# SolenoidController.net
KiCad netlist of a schematic drawn in EAGLE
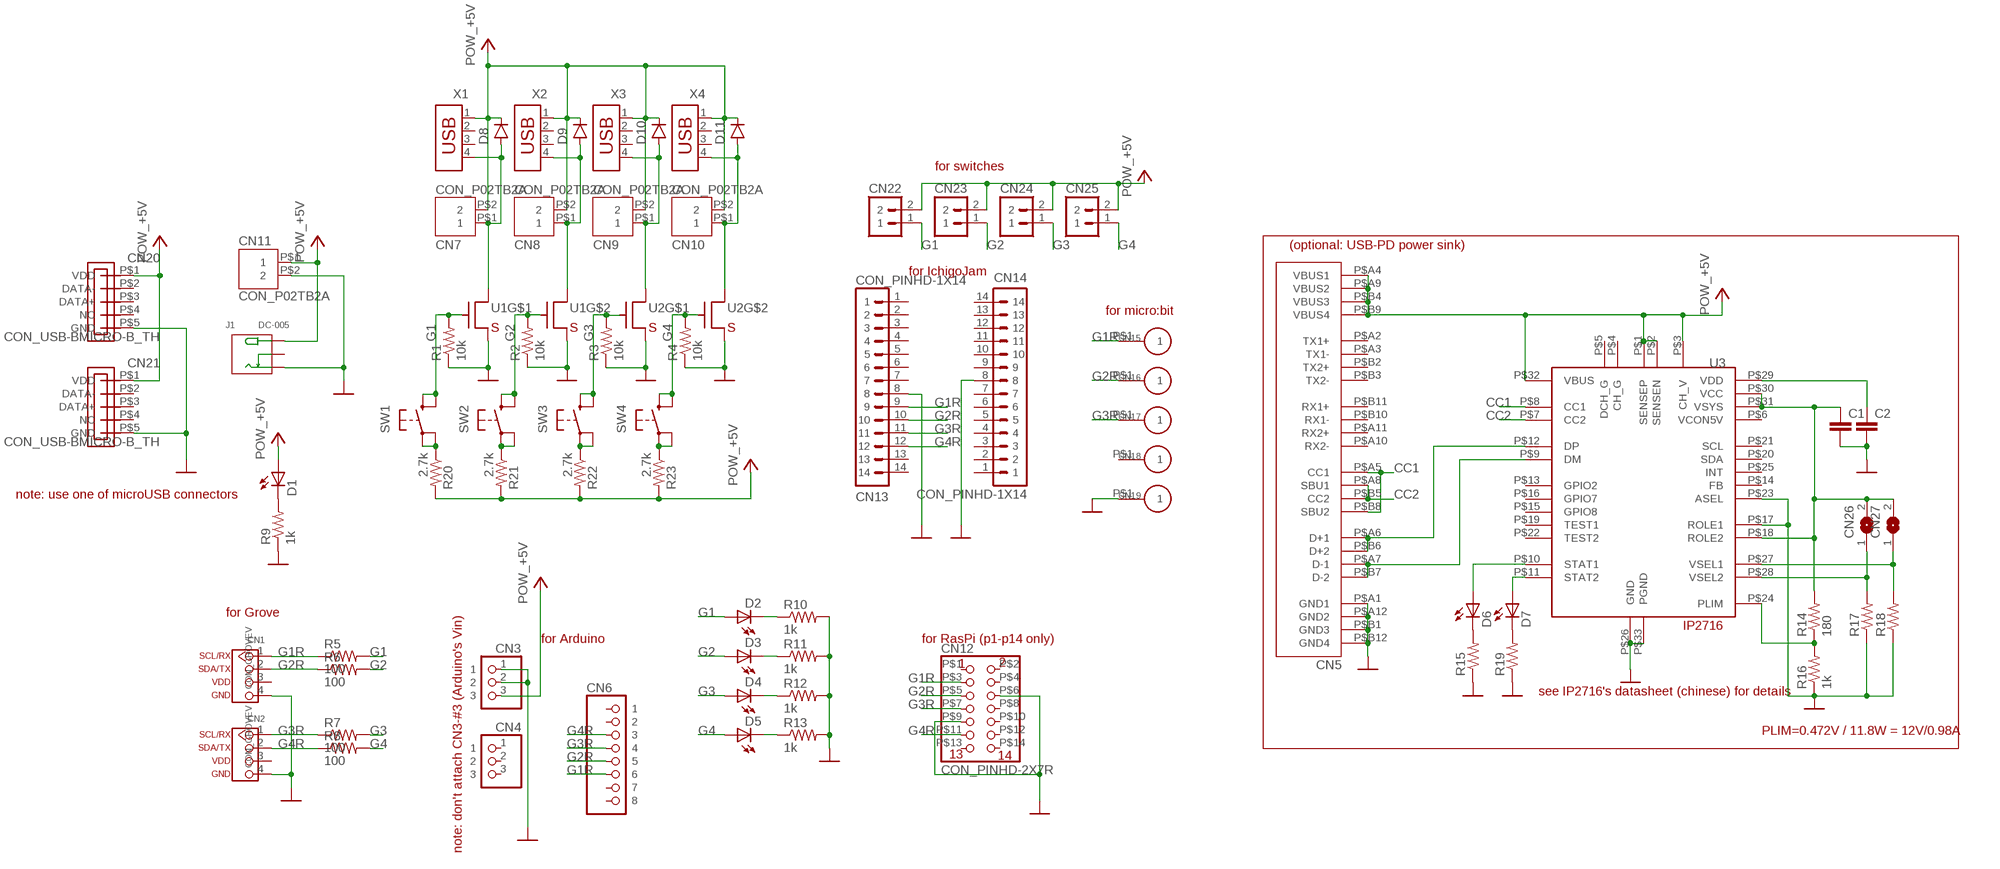
[diagram p0: schematic, sheet 1]

(export (version "E")
  (design (tool "Eeschema 10.0.6"))
  (components
    (comp (ref "C1")
      (value "CAP0603")
      (footprint "eagle-import:0603")
      (libsource (lib "eagle-import") (part "CAP0603"))
    )
    (comp (ref "C2")
      (value "CAP0603")
      (footprint "eagle-import:0603")
      (libsource (lib "eagle-import") (part "CAP0603"))
    )
    (comp (ref "CN1")
      (value "CON_GROVEV")
      (footprint "eagle-import:CON_GROVE_V")
      (libsource (lib "eagle-import") (part "CON_GROVEV"))
    )
    (comp (ref "CN2")
      (value "CON_GROVEV")
      (footprint "eagle-import:CON_GROVE_V")
      (libsource (lib "eagle-import") (part "CON_GROVEV"))
    )
    (comp (ref "CN3")
      (value "CON_PINHD-1X3R")
      (footprint "eagle-import:1X03R")
      (libsource (lib "eagle-import") (part "CON_PINHD-1X3R"))
    )
    (comp (ref "CN4")
      (value "CON_PINHD-1X3R")
      (footprint "eagle-import:1X03R")
      (libsource (lib "eagle-import") (part "CON_PINHD-1X3R"))
    )
    (comp (ref "CN5")
      (value "CON_USB-C")
      (footprint "eagle-import:USB-C_24P")
      (libsource (lib "eagle-import") (part "CON_USB-C"))
    )
    (comp (ref "CN6")
      (value "CON_PINHD-1X8R")
      (footprint "eagle-import:1X08R")
      (libsource (lib "eagle-import") (part "CON_PINHD-1X8R"))
    )
    (comp (ref "CN7")
      (value "CON_P02TB2A")
      (footprint "eagle-import:TERM_BLOCK_2P")
      (libsource (lib "eagle-import") (part "CON_P02TB2A"))
    )
    (comp (ref "CN8")
      (value "CON_P02TB2A")
      (footprint "eagle-import:TERM_BLOCK_2P")
      (libsource (lib "eagle-import") (part "CON_P02TB2A"))
    )
    (comp (ref "CN9")
      (value "CON_P02TB2A")
      (footprint "eagle-import:TERM_BLOCK_2P")
      (libsource (lib "eagle-import") (part "CON_P02TB2A"))
    )
    (comp (ref "CN10")
      (value "CON_P02TB2A")
      (footprint "eagle-import:TERM_BLOCK_2P")
      (libsource (lib "eagle-import") (part "CON_P02TB2A"))
    )
    (comp (ref "CN11")
      (value "CON_P02TB2A")
      (footprint "eagle-import:TERM_BLOCK_2P")
      (libsource (lib "eagle-import") (part "CON_P02TB2A"))
    )
    (comp (ref "CN12")
      (value "CON_PINHD-2X7R")
      (footprint "eagle-import:2X7R")
      (libsource (lib "eagle-import") (part "CON_PINHD-2X7R"))
    )
    (comp (ref "CN13")
      (value "CON_PINHD-1X14")
      (footprint "eagle-import:1X14")
      (libsource (lib "eagle-import") (part "CON_PINHD-1X14"))
    )
    (comp (ref "CN14")
      (value "CON_PINHD-1X14")
      (footprint "eagle-import:1X14")
      (libsource (lib "eagle-import") (part "CON_PINHD-1X14"))
    )
    (comp (ref "CN15")
      (value "CON_P01TH04MM")
      (footprint "eagle-import:TH4MM")
      (libsource (lib "eagle-import") (part "CON_P01TH04MM"))
    )
    (comp (ref "CN16")
      (value "CON_P01TH04MM")
      (footprint "eagle-import:TH4MM")
      (libsource (lib "eagle-import") (part "CON_P01TH04MM"))
    )
    (comp (ref "CN17")
      (value "CON_P01TH04MM")
      (footprint "eagle-import:TH4MM")
      (libsource (lib "eagle-import") (part "CON_P01TH04MM"))
    )
    (comp (ref "CN18")
      (value "CON_P01TH04MM")
      (footprint "eagle-import:TH4MM")
      (libsource (lib "eagle-import") (part "CON_P01TH04MM"))
    )
    (comp (ref "CN19")
      (value "CON_P01TH04MM")
      (footprint "eagle-import:TH4MM")
      (libsource (lib "eagle-import") (part "CON_P01TH04MM"))
    )
    (comp (ref "CN20")
      (value "CON_USB-BMICRO-B_TH")
      (footprint "eagle-import:USB-MICROB-TH")
      (libsource (lib "eagle-import") (part "CON_USB-BMICRO-B_TH"))
    )
    (comp (ref "CN21")
      (value "CON_USB-BMICRO-B_TH")
      (footprint "eagle-import:USB-MICROB-TH")
      (libsource (lib "eagle-import") (part "CON_USB-BMICRO-B_TH"))
    )
    (comp (ref "CN22")
      (value "CON_PINHD-1X2PTH")
      (footprint "eagle-import:SPARKFUN_1X02")
      (libsource (lib "eagle-import") (part "CON_PINHD-1X2PTH"))
    )
    (comp (ref "CN23")
      (value "CON_PINHD-1X2PTH")
      (footprint "eagle-import:SPARKFUN_1X02")
      (libsource (lib "eagle-import") (part "CON_PINHD-1X2PTH"))
    )
    (comp (ref "CN24")
      (value "CON_PINHD-1X2PTH")
      (footprint "eagle-import:SPARKFUN_1X02")
      (libsource (lib "eagle-import") (part "CON_PINHD-1X2PTH"))
    )
    (comp (ref "CN25")
      (value "CON_PINHD-1X2PTH")
      (footprint "eagle-import:SPARKFUN_1X02")
      (libsource (lib "eagle-import") (part "CON_PINHD-1X2PTH"))
    )
    (comp (ref "CN26")
      (value "JUMPER_SJ")
      (footprint "eagle-import:JUMPER_SJ")
      (libsource (lib "eagle-import") (part "JUMPER_SJ"))
    )
    (comp (ref "CN27")
      (value "JUMPER_SJ")
      (footprint "eagle-import:JUMPER_SJ")
      (libsource (lib "eagle-import") (part "JUMPER_SJ"))
    )
    (comp (ref "D1")
      (value "LED5MM")
      (footprint "eagle-import:SPARKFUN_LED5MM")
      (libsource (lib "eagle-import") (part "LED5MM"))
    )
    (comp (ref "D2")
      (value "LED5MM")
      (footprint "eagle-import:SPARKFUN_LED5MM")
      (libsource (lib "eagle-import") (part "LED5MM"))
    )
    (comp (ref "D3")
      (value "LED5MM")
      (footprint "eagle-import:SPARKFUN_LED5MM")
      (libsource (lib "eagle-import") (part "LED5MM"))
    )
    (comp (ref "D4")
      (value "LED5MM")
      (footprint "eagle-import:SPARKFUN_LED5MM")
      (libsource (lib "eagle-import") (part "LED5MM"))
    )
    (comp (ref "D5")
      (value "LED5MM")
      (footprint "eagle-import:SPARKFUN_LED5MM")
      (libsource (lib "eagle-import") (part "LED5MM"))
    )
    (comp (ref "D6")
      (value "LED0603")
      (footprint "eagle-import:SPARKFUN_LED-0603")
      (libsource (lib "eagle-import") (part "LED0603"))
    )
    (comp (ref "D7")
      (value "LED0603")
      (footprint "eagle-import:SPARKFUN_LED-0603")
      (libsource (lib "eagle-import") (part "LED0603"))
    )
    (comp (ref "D8")
      (value "DIODESOD123FL")
      (footprint "eagle-import:SOD123FL")
      (libsource (lib "eagle-import") (part "DIODESOD123FL"))
    )
    (comp (ref "D9")
      (value "DIODESOD123FL")
      (footprint "eagle-import:SOD123FL")
      (libsource (lib "eagle-import") (part "DIODESOD123FL"))
    )
    (comp (ref "D10")
      (value "DIODESOD123FL")
      (footprint "eagle-import:SOD123FL")
      (libsource (lib "eagle-import") (part "DIODESOD123FL"))
    )
    (comp (ref "D11")
      (value "DIODESOD123FL")
      (footprint "eagle-import:SOD123FL")
      (libsource (lib "eagle-import") (part "DIODESOD123FL"))
    )
    (comp (ref "J1")
      (value "DC-005")
      (footprint "eagle-import:DCJ3P-14.2X11.0X9.0MM")
      (libsource (lib "eagle-import") (part "CONN-POWER-JACK-2.1MM(DC-005)"))
    )
    (comp (ref "R1")
      (value "10k")
      (footprint "eagle-import:0603")
      (libsource (lib "eagle-import") (part "RES0603"))
    )
    (comp (ref "R2")
      (value "10k")
      (footprint "eagle-import:0603")
      (libsource (lib "eagle-import") (part "RES0603"))
    )
    (comp (ref "R3")
      (value "10k")
      (footprint "eagle-import:0603")
      (libsource (lib "eagle-import") (part "RES0603"))
    )
    (comp (ref "R4")
      (value "10k")
      (footprint "eagle-import:0603")
      (libsource (lib "eagle-import") (part "RES0603"))
    )
    (comp (ref "R5")
      (value "100")
      (footprint "eagle-import:0603")
      (libsource (lib "eagle-import") (part "RES0603"))
    )
    (comp (ref "R6")
      (value "100")
      (footprint "eagle-import:0603")
      (libsource (lib "eagle-import") (part "RES0603"))
    )
    (comp (ref "R7")
      (value "100")
      (footprint "eagle-import:0603")
      (libsource (lib "eagle-import") (part "RES0603"))
    )
    (comp (ref "R8")
      (value "100")
      (footprint "eagle-import:0603")
      (libsource (lib "eagle-import") (part "RES0603"))
    )
    (comp (ref "R9")
      (value "1k")
      (footprint "eagle-import:0603")
      (libsource (lib "eagle-import") (part "RES0603"))
    )
    (comp (ref "R10")
      (value "1k")
      (footprint "eagle-import:0603")
      (libsource (lib "eagle-import") (part "RES0603"))
    )
    (comp (ref "R11")
      (value "1k")
      (footprint "eagle-import:0603")
      (libsource (lib "eagle-import") (part "RES0603"))
    )
    (comp (ref "R12")
      (value "1k")
      (footprint "eagle-import:0603")
      (libsource (lib "eagle-import") (part "RES0603"))
    )
    (comp (ref "R13")
      (value "1k")
      (footprint "eagle-import:0603")
      (libsource (lib "eagle-import") (part "RES0603"))
    )
    (comp (ref "R14")
      (value "180")
      (footprint "eagle-import:0603")
      (libsource (lib "eagle-import") (part "RES0603"))
    )
    (comp (ref "R15")
      (value "RES0603")
      (footprint "eagle-import:0603")
      (libsource (lib "eagle-import") (part "RES0603"))
    )
    (comp (ref "R16")
      (value "1k")
      (footprint "eagle-import:0603")
      (libsource (lib "eagle-import") (part "RES0603"))
    )
    (comp (ref "R17")
      (value "RES0603")
      (footprint "eagle-import:0603")
      (libsource (lib "eagle-import") (part "RES0603"))
    )
    (comp (ref "R18")
      (value "RES0603")
      (footprint "eagle-import:0603")
      (libsource (lib "eagle-import") (part "RES0603"))
    )
    (comp (ref "R19")
      (value "RES0603")
      (footprint "eagle-import:0603")
      (libsource (lib "eagle-import") (part "RES0603"))
    )
    (comp (ref "R20")
      (value "2.7k")
      (footprint "eagle-import:0603")
      (libsource (lib "eagle-import") (part "RES0603"))
    )
    (comp (ref "R21")
      (value "2.7k")
      (footprint "eagle-import:0603")
      (libsource (lib "eagle-import") (part "RES0603"))
    )
    (comp (ref "R22")
      (value "2.7k")
      (footprint "eagle-import:0603")
      (libsource (lib "eagle-import") (part "RES0603"))
    )
    (comp (ref "R23")
      (value "2.7k")
      (footprint "eagle-import:0603")
      (libsource (lib "eagle-import") (part "RES0603"))
    )
    (comp (ref "SW1")
      (value "SW_TACTSMD_B3FS4")
      (footprint "eagle-import:SW_B3FS-4")
      (libsource (lib "eagle-import") (part "SW_TACTSMD_B3FS4"))
    )
    (comp (ref "SW2")
      (value "SW_TACTSMD_B3FS4")
      (footprint "eagle-import:SW_B3FS-4")
      (libsource (lib "eagle-import") (part "SW_TACTSMD_B3FS4"))
    )
    (comp (ref "SW3")
      (value "SW_TACTSMD_B3FS4")
      (footprint "eagle-import:SW_B3FS-4")
      (libsource (lib "eagle-import") (part "SW_TACTSMD_B3FS4"))
    )
    (comp (ref "SW4")
      (value "SW_TACTSMD_B3FS4")
      (footprint "eagle-import:SW_B3FS-4")
      (libsource (lib "eagle-import") (part "SW_TACTSMD_B3FS4"))
    )
    (comp (ref "U1")
      (value "TR_NMOS_IRF7103")
      (footprint "eagle-import:SO08")
      (libsource (lib "eagle-import") (part "TR_NMOS_IRF7103"))
    )
    (comp (ref "U2")
      (value "TR_NMOS_IRF7103")
      (footprint "eagle-import:SO08")
      (libsource (lib "eagle-import") (part "TR_NMOS_IRF7103"))
    )
    (comp (ref "U3")
      (value "PMU_IP2716")
      (footprint "eagle-import:QFN32E")
      (libsource (lib "eagle-import") (part "PMU_IP2716"))
    )
    (comp (ref "X1")
      (value "CON_USB-A")
      (footprint "eagle-import:USB-A")
      (libsource (lib "eagle-import") (part "CON_USB-A"))
    )
    (comp (ref "X2")
      (value "CON_USB-A")
      (footprint "eagle-import:USB-A")
      (libsource (lib "eagle-import") (part "CON_USB-A"))
    )
    (comp (ref "X3")
      (value "CON_USB-A")
      (footprint "eagle-import:USB-A")
      (libsource (lib "eagle-import") (part "CON_USB-A"))
    )
    (comp (ref "X4")
      (value "CON_USB-A")
      (footprint "eagle-import:USB-A")
      (libsource (lib "eagle-import") (part "CON_USB-A"))
    )
  )
  (nets
    (net (code "1") (name "/CC1") (class "Default")
      (node (ref "CN5") (pin "P$A5") (pinfunction "CC1_P$A5") (pintype "bidirectional"))
      (node (ref "CN5") (pin "P$B8") (pinfunction "SBU2_P$B8") (pintype "bidirectional"))
      (node (ref "U3") (pin "P$8") (pinfunction "CC1_P$8") (pintype "bidirectional"))
    )
    (net (code "2") (name "/CC2") (class "Default")
      (node (ref "CN5") (pin "P$A8") (pinfunction "SBU1_P$A8") (pintype "bidirectional"))
      (node (ref "CN5") (pin "P$B5") (pinfunction "CC2_P$B5") (pintype "bidirectional"))
      (node (ref "U3") (pin "P$7") (pinfunction "CC2_P$7") (pintype "bidirectional"))
    )
    (net (code "3") (name "/G1") (class "Default")
      (node (ref "CN22") (pin "1") (pinfunction "1_1") (pintype "passive"))
      (node (ref "D2") (pin "A") (pinfunction "A_A") (pintype "passive"))
      (node (ref "R1") (pin "2") (pinfunction "2_2") (pintype "passive"))
      (node (ref "R5") (pin "2") (pinfunction "2_2") (pintype "passive"))
      (node (ref "SW1") (pin "P$3") (pinfunction "S_P$3") (pintype "passive"))
      (node (ref "SW1") (pin "P$4") (pinfunction "S1_P$4") (pintype "passive"))
      (node (ref "U1") (pin "2") (pinfunction "G_2") (pintype "bidirectional"))
    )
    (net (code "4") (name "/G1R") (class "Default")
      (node (ref "CN1") (pin "1") (pinfunction "1_1") (pintype "bidirectional"))
      (node (ref "CN12") (pin "P$3") (pinfunction "3_P$3") (pintype "passive"))
      (node (ref "CN13") (pin "9") (pinfunction "9_9") (pintype "passive"))
      (node (ref "CN15") (pin "P$1") (pinfunction "1_P$1") (pintype "bidirectional"))
      (node (ref "CN6") (pin "6") (pinfunction "6_6") (pintype "passive"))
      (node (ref "R5") (pin "1") (pinfunction "1_1") (pintype "passive"))
    )
    (net (code "5") (name "/G2") (class "Default")
      (node (ref "CN23") (pin "1") (pinfunction "1_1") (pintype "passive"))
      (node (ref "D3") (pin "A") (pinfunction "A_A") (pintype "passive"))
      (node (ref "R2") (pin "2") (pinfunction "2_2") (pintype "passive"))
      (node (ref "R6") (pin "2") (pinfunction "2_2") (pintype "passive"))
      (node (ref "SW2") (pin "P$3") (pinfunction "S_P$3") (pintype "passive"))
      (node (ref "SW2") (pin "P$4") (pinfunction "S1_P$4") (pintype "passive"))
      (node (ref "U1") (pin "4") (pinfunction "G_4") (pintype "bidirectional"))
    )
    (net (code "6") (name "/G2R") (class "Default")
      (node (ref "CN1") (pin "2") (pinfunction "2_2") (pintype "bidirectional"))
      (node (ref "CN12") (pin "P$5") (pinfunction "5_P$5") (pintype "passive"))
      (node (ref "CN13") (pin "10") (pinfunction "10_10") (pintype "passive"))
      (node (ref "CN16") (pin "P$1") (pinfunction "1_P$1") (pintype "bidirectional"))
      (node (ref "CN6") (pin "5") (pinfunction "5_5") (pintype "passive"))
      (node (ref "R6") (pin "1") (pinfunction "1_1") (pintype "passive"))
    )
    (net (code "7") (name "/G3") (class "Default")
      (node (ref "CN24") (pin "1") (pinfunction "1_1") (pintype "passive"))
      (node (ref "D4") (pin "A") (pinfunction "A_A") (pintype "passive"))
      (node (ref "R3") (pin "2") (pinfunction "2_2") (pintype "passive"))
      (node (ref "R7") (pin "2") (pinfunction "2_2") (pintype "passive"))
      (node (ref "SW3") (pin "P$3") (pinfunction "S_P$3") (pintype "passive"))
      (node (ref "SW3") (pin "P$4") (pinfunction "S1_P$4") (pintype "passive"))
      (node (ref "U2") (pin "2") (pinfunction "G_2") (pintype "bidirectional"))
    )
    (net (code "8") (name "/G3R") (class "Default")
      (node (ref "CN12") (pin "P$7") (pinfunction "7_P$7") (pintype "passive"))
      (node (ref "CN13") (pin "11") (pinfunction "11_11") (pintype "passive"))
      (node (ref "CN17") (pin "P$1") (pinfunction "1_P$1") (pintype "bidirectional"))
      (node (ref "CN2") (pin "1") (pinfunction "1_1") (pintype "bidirectional"))
      (node (ref "CN6") (pin "4") (pinfunction "4_4") (pintype "passive"))
      (node (ref "R7") (pin "1") (pinfunction "1_1") (pintype "passive"))
    )
    (net (code "9") (name "/G4") (class "Default")
      (node (ref "CN25") (pin "1") (pinfunction "1_1") (pintype "passive"))
      (node (ref "D5") (pin "A") (pinfunction "A_A") (pintype "passive"))
      (node (ref "R4") (pin "2") (pinfunction "2_2") (pintype "passive"))
      (node (ref "R8") (pin "2") (pinfunction "2_2") (pintype "passive"))
      (node (ref "SW4") (pin "P$3") (pinfunction "S_P$3") (pintype "passive"))
      (node (ref "SW4") (pin "P$4") (pinfunction "S1_P$4") (pintype "passive"))
      (node (ref "U2") (pin "4") (pinfunction "G_4") (pintype "bidirectional"))
    )
    (net (code "10") (name "/G4R") (class "Default")
      (node (ref "CN12") (pin "P$11") (pinfunction "11_P$11") (pintype "passive"))
      (node (ref "CN13") (pin "12") (pinfunction "12_12") (pintype "passive"))
      (node (ref "CN2") (pin "2") (pinfunction "2_2") (pintype "bidirectional"))
      (node (ref "CN6") (pin "3") (pinfunction "3_3") (pintype "passive"))
      (node (ref "R8") (pin "1") (pinfunction "1_1") (pintype "passive"))
    )
    (net (code "11") (name "Net-(CN5-D+1)") (class "Default")
      (node (ref "CN5") (pin "P$A6") (pinfunction "D+1_P$A6") (pintype "bidirectional"))
      (node (ref "CN5") (pin "P$B6") (pinfunction "D+2_P$B6") (pintype "bidirectional"))
      (node (ref "U3") (pin "P$12") (pinfunction "DP_P$12") (pintype "bidirectional"))
    )
    (net (code "12") (name "Net-(CN5-D-1)") (class "Default")
      (node (ref "CN5") (pin "P$A7") (pinfunction "D-1_P$A7") (pintype "bidirectional"))
      (node (ref "CN5") (pin "P$B7") (pinfunction "D-2_P$B7") (pintype "bidirectional"))
      (node (ref "U3") (pin "P$9") (pinfunction "DM_P$9") (pintype "bidirectional"))
    )
    (net (code "13") (name "Net-(CN7-1)") (class "Default")
      (node (ref "CN7") (pin "P$1") (pinfunction "1_P$1") (pintype "passive"))
      (node (ref "D8") (pin "P$A") (pinfunction "P$A_P$A") (pintype "bidirectional"))
      (node (ref "U1") (pin "7") (pinfunction "D_7") (pintype "bidirectional"))
      (node (ref "X1") (pin "4") (pinfunction "4_4") (pintype "passive"))
    )
    (net (code "14") (name "Net-(CN8-1)") (class "Default")
      (node (ref "CN8") (pin "P$1") (pinfunction "1_P$1") (pintype "passive"))
      (node (ref "D9") (pin "P$A") (pinfunction "P$A_P$A") (pintype "bidirectional"))
      (node (ref "U1") (pin "5") (pinfunction "D_5") (pintype "bidirectional"))
      (node (ref "X2") (pin "4") (pinfunction "4_4") (pintype "passive"))
    )
    (net (code "15") (name "Net-(CN9-1)") (class "Default")
      (node (ref "CN9") (pin "P$1") (pinfunction "1_P$1") (pintype "passive"))
      (node (ref "D10") (pin "P$A") (pinfunction "P$A_P$A") (pintype "bidirectional"))
      (node (ref "U2") (pin "7") (pinfunction "D_7") (pintype "bidirectional"))
      (node (ref "X3") (pin "4") (pinfunction "4_4") (pintype "passive"))
    )
    (net (code "16") (name "Net-(CN10-1)") (class "Default")
      (node (ref "CN10") (pin "P$1") (pinfunction "1_P$1") (pintype "passive"))
      (node (ref "D11") (pin "P$A") (pinfunction "P$A_P$A") (pintype "bidirectional"))
      (node (ref "U2") (pin "5") (pinfunction "D_5") (pintype "bidirectional"))
      (node (ref "X4") (pin "4") (pinfunction "4_4") (pintype "passive"))
    )
    (net (code "17") (name "Net-(D1-C)") (class "Default")
      (node (ref "D1") (pin "K") (pinfunction "C_K") (pintype "passive"))
      (node (ref "R9") (pin "2") (pinfunction "2_2") (pintype "passive"))
    )
    (net (code "18") (name "Net-(D2-C)") (class "Default")
      (node (ref "D2") (pin "K") (pinfunction "C_K") (pintype "passive"))
      (node (ref "R10") (pin "1") (pinfunction "1_1") (pintype "passive"))
    )
    (net (code "19") (name "Net-(D3-C)") (class "Default")
      (node (ref "D3") (pin "K") (pinfunction "C_K") (pintype "passive"))
      (node (ref "R11") (pin "1") (pinfunction "1_1") (pintype "passive"))
    )
    (net (code "20") (name "Net-(D4-C)") (class "Default")
      (node (ref "D4") (pin "K") (pinfunction "C_K") (pintype "passive"))
      (node (ref "R12") (pin "1") (pinfunction "1_1") (pintype "passive"))
    )
    (net (code "21") (name "Net-(D5-C)") (class "Default")
      (node (ref "D5") (pin "K") (pinfunction "C_K") (pintype "passive"))
      (node (ref "R13") (pin "1") (pinfunction "1_1") (pintype "passive"))
    )
    (net (code "22") (name "Net-(D6-PadC)") (class "Default")
      (node (ref "D6") (pin "C") (pinfunction "C_C") (pintype "passive"))
      (node (ref "R15") (pin "2") (pinfunction "2_2") (pintype "passive"))
    )
    (net (code "23") (name "Net-(D7-PadC)") (class "Default")
      (node (ref "D7") (pin "C") (pinfunction "C_C") (pintype "passive"))
      (node (ref "R19") (pin "2") (pinfunction "2_2") (pintype "passive"))
    )
    (net (code "24") (name "Net-(SW1-P)") (class "Default")
      (node (ref "R20") (pin "1") (pinfunction "1_1") (pintype "passive"))
      (node (ref "SW1") (pin "P$1") (pinfunction "P_P$1") (pintype "passive"))
      (node (ref "SW1") (pin "P$2") (pinfunction "P1_P$2") (pintype "passive"))
    )
    (net (code "25") (name "Net-(SW2-P)") (class "Default")
      (node (ref "R21") (pin "1") (pinfunction "1_1") (pintype "passive"))
      (node (ref "SW2") (pin "P$1") (pinfunction "P_P$1") (pintype "passive"))
      (node (ref "SW2") (pin "P$2") (pinfunction "P1_P$2") (pintype "passive"))
    )
    (net (code "26") (name "Net-(SW3-P)") (class "Default")
      (node (ref "R22") (pin "1") (pinfunction "1_1") (pintype "passive"))
      (node (ref "SW3") (pin "P$1") (pinfunction "P_P$1") (pintype "passive"))
      (node (ref "SW3") (pin "P$2") (pinfunction "P1_P$2") (pintype "passive"))
    )
    (net (code "27") (name "Net-(SW4-P)") (class "Default")
      (node (ref "R23") (pin "1") (pinfunction "1_1") (pintype "passive"))
      (node (ref "SW4") (pin "P$1") (pinfunction "P_P$1") (pintype "passive"))
      (node (ref "SW4") (pin "P$2") (pinfunction "P1_P$2") (pintype "passive"))
    )
    (net (code "28") (name "Net-(U3-PLIM)") (class "Default")
      (node (ref "R14") (pin "1") (pinfunction "1_1") (pintype "passive"))
      (node (ref "R16") (pin "2") (pinfunction "2_2") (pintype "passive"))
      (node (ref "U3") (pin "P$24") (pinfunction "PLIM_P$24") (pintype "bidirectional"))
    )
    (net (code "29") (name "Net-(U3-ROLE2)") (class "Default")
      (node (ref "C1") (pin "1") (pinfunction "1_1") (pintype "passive"))
      (node (ref "CN26") (pin "2") (pinfunction "2_2") (pintype "passive"))
      (node (ref "CN27") (pin "2") (pinfunction "2_2") (pintype "passive"))
      (node (ref "R14") (pin "2") (pinfunction "2_2") (pintype "passive"))
      (node (ref "U3") (pin "P$18") (pinfunction "ROLE2_P$18") (pintype "bidirectional"))
      (node (ref "U3") (pin "P$30") (pinfunction "VCC_P$30") (pintype "bidirectional"))
      (node (ref "U3") (pin "P$31") (pinfunction "VSYS_P$31") (pintype "bidirectional"))
    )
    (net (code "30") (name "Net-(U3-STAT1)") (class "Default")
      (node (ref "D6") (pin "A") (pinfunction "A_A") (pintype "passive"))
      (node (ref "U3") (pin "P$10") (pinfunction "STAT1_P$10") (pintype "bidirectional"))
    )
    (net (code "31") (name "Net-(U3-STAT2)") (class "Default")
      (node (ref "D7") (pin "A") (pinfunction "A_A") (pintype "passive"))
      (node (ref "U3") (pin "P$11") (pinfunction "STAT2_P$11") (pintype "bidirectional"))
    )
    (net (code "32") (name "Net-(U3-VDD)") (class "Default")
      (node (ref "C2") (pin "1") (pinfunction "1_1") (pintype "passive"))
      (node (ref "U3") (pin "P$29") (pinfunction "VDD_P$29") (pintype "bidirectional"))
    )
    (net (code "33") (name "Net-(U3-VSEL1)") (class "Default")
      (node (ref "CN27") (pin "1") (pinfunction "1_1") (pintype "passive"))
      (node (ref "R18") (pin "2") (pinfunction "2_2") (pintype "passive"))
      (node (ref "U3") (pin "P$27") (pinfunction "VSEL1_P$27") (pintype "bidirectional"))
    )
    (net (code "34") (name "Net-(U3-VSEL2)") (class "Default")
      (node (ref "CN26") (pin "1") (pinfunction "1_1") (pintype "passive"))
      (node (ref "R17") (pin "2") (pinfunction "2_2") (pintype "passive"))
      (node (ref "U3") (pin "P$28") (pinfunction "VSEL2_P$28") (pintype "bidirectional"))
    )
    (net (code "35") (name "POW_+5V") (class "Default")
      (node (ref "CN10") (pin "P$2") (pinfunction "2_P$2") (pintype "passive"))
      (node (ref "CN11") (pin "P$1") (pinfunction "1_P$1") (pintype "passive"))
      (node (ref "CN20") (pin "P$1") (pinfunction "VDD_P$1") (pintype "power_in"))
      (node (ref "CN21") (pin "P$1") (pinfunction "VDD_P$1") (pintype "power_in"))
      (node (ref "CN22") (pin "2") (pinfunction "2_2") (pintype "passive"))
      (node (ref "CN23") (pin "2") (pinfunction "2_2") (pintype "passive"))
      (node (ref "CN24") (pin "2") (pinfunction "2_2") (pintype "passive"))
      (node (ref "CN25") (pin "2") (pinfunction "2_2") (pintype "passive"))
      (node (ref "CN3") (pin "3") (pinfunction "3_3") (pintype "passive"))
      (node (ref "CN5") (pin "P$A4") (pinfunction "VBUS1_P$A4") (pintype "bidirectional"))
      (node (ref "CN5") (pin "P$A9") (pinfunction "VBUS2_P$A9") (pintype "bidirectional"))
      (node (ref "CN5") (pin "P$B4") (pinfunction "VBUS3_P$B4") (pintype "bidirectional"))
      (node (ref "CN5") (pin "P$B9") (pinfunction "VBUS4_P$B9") (pintype "bidirectional"))
      (node (ref "CN7") (pin "P$2") (pinfunction "2_P$2") (pintype "passive"))
      (node (ref "CN8") (pin "P$2") (pinfunction "2_P$2") (pintype "passive"))
      (node (ref "CN9") (pin "P$2") (pinfunction "2_P$2") (pintype "passive"))
      (node (ref "D1") (pin "A") (pinfunction "A_A") (pintype "passive"))
      (node (ref "D10") (pin "P$K") (pinfunction "P$K_P$K") (pintype "bidirectional"))
      (node (ref "D11") (pin "P$K") (pinfunction "P$K_P$K") (pintype "bidirectional"))
      (node (ref "D8") (pin "P$K") (pinfunction "P$K_P$K") (pintype "bidirectional"))
      (node (ref "D9") (pin "P$K") (pinfunction "P$K_P$K") (pintype "bidirectional"))
      (node (ref "J1") (pin "+") (pinfunction "+_+") (pintype "bidirectional"))
      (node (ref "R20") (pin "2") (pinfunction "2_2") (pintype "passive"))
      (node (ref "R21") (pin "2") (pinfunction "2_2") (pintype "passive"))
      (node (ref "R22") (pin "2") (pinfunction "2_2") (pintype "passive"))
      (node (ref "R23") (pin "2") (pinfunction "2_2") (pintype "passive"))
      (node (ref "U3") (pin "P$1") (pinfunction "SENSEP_P$1") (pintype "bidirectional"))
      (node (ref "U3") (pin "P$2") (pinfunction "SENSEN_P$2") (pintype "bidirectional"))
      (node (ref "U3") (pin "P$3") (pinfunction "CH_V_P$3") (pintype "bidirectional"))
      (node (ref "U3") (pin "P$32") (pinfunction "VBUS_P$32") (pintype "bidirectional"))
      (node (ref "X1") (pin "1") (pinfunction "1_1") (pintype "passive"))
      (node (ref "X2") (pin "1") (pinfunction "1_1") (pintype "passive"))
      (node (ref "X3") (pin "1") (pinfunction "1_1") (pintype "passive"))
      (node (ref "X4") (pin "1") (pinfunction "1_1") (pintype "passive"))
    )
    (net (code "36") (name "POW_GND") (class "Default")
      (node (ref "C1") (pin "2") (pinfunction "2_2") (pintype "passive"))
      (node (ref "C2") (pin "2") (pinfunction "2_2") (pintype "passive"))
      (node (ref "CN1") (pin "4") (pinfunction "4_4") (pintype "bidirectional"))
      (node (ref "CN11") (pin "P$2") (pinfunction "2_P$2") (pintype "passive"))
      (node (ref "CN12") (pin "P$6") (pinfunction "6_P$6") (pintype "passive"))
      (node (ref "CN12") (pin "P$9") (pinfunction "9_P$9") (pintype "passive"))
      (node (ref "CN13") (pin "8") (pinfunction "8_8") (pintype "passive"))
      (node (ref "CN14") (pin "8") (pinfunction "8_8") (pintype "passive"))
      (node (ref "CN19") (pin "P$1") (pinfunction "1_P$1") (pintype "bidirectional"))
      (node (ref "CN2") (pin "4") (pinfunction "4_4") (pintype "bidirectional"))
      (node (ref "CN20") (pin "P$5") (pinfunction "GND_P$5") (pintype "power_in"))
      (node (ref "CN21") (pin "P$5") (pinfunction "GND_P$5") (pintype "power_in"))
      (node (ref "CN3") (pin "1") (pinfunction "1_1") (pintype "passive"))
      (node (ref "CN3") (pin "2") (pinfunction "2_2") (pintype "passive"))
      (node (ref "CN5") (pin "P$A1") (pinfunction "GND1_P$A1") (pintype "bidirectional"))
      (node (ref "CN5") (pin "P$A12") (pinfunction "GND2_P$A12") (pintype "bidirectional"))
      (node (ref "CN5") (pin "P$B1") (pinfunction "GND3_P$B1") (pintype "bidirectional"))
      (node (ref "CN5") (pin "P$B12") (pinfunction "GND4_P$B12") (pintype "bidirectional"))
      (node (ref "J1") (pin "-1") (pinfunction "-_-1") (pintype "bidirectional"))
      (node (ref "R1") (pin "1") (pinfunction "1_1") (pintype "passive"))
      (node (ref "R10") (pin "2") (pinfunction "2_2") (pintype "passive"))
      (node (ref "R11") (pin "2") (pinfunction "2_2") (pintype "passive"))
      (node (ref "R12") (pin "2") (pinfunction "2_2") (pintype "passive"))
      (node (ref "R13") (pin "2") (pinfunction "2_2") (pintype "passive"))
      (node (ref "R15") (pin "1") (pinfunction "1_1") (pintype "passive"))
      (node (ref "R16") (pin "1") (pinfunction "1_1") (pintype "passive"))
      (node (ref "R17") (pin "1") (pinfunction "1_1") (pintype "passive"))
      (node (ref "R18") (pin "1") (pinfunction "1_1") (pintype "passive"))
      (node (ref "R19") (pin "1") (pinfunction "1_1") (pintype "passive"))
      (node (ref "R2") (pin "1") (pinfunction "1_1") (pintype "passive"))
      (node (ref "R3") (pin "1") (pinfunction "1_1") (pintype "passive"))
      (node (ref "R4") (pin "1") (pinfunction "1_1") (pintype "passive"))
      (node (ref "R9") (pin "1") (pinfunction "1_1") (pintype "passive"))
      (node (ref "U1") (pin "1") (pinfunction "S_1") (pintype "bidirectional"))
      (node (ref "U1") (pin "3") (pinfunction "S_3") (pintype "bidirectional"))
      (node (ref "U2") (pin "1") (pinfunction "S_1") (pintype "bidirectional"))
      (node (ref "U2") (pin "3") (pinfunction "S_3") (pintype "bidirectional"))
      (node (ref "U3") (pin "P$17") (pinfunction "ROLE1_P$17") (pintype "bidirectional"))
      (node (ref "U3") (pin "P$23") (pinfunction "ASEL_P$23") (pintype "bidirectional"))
      (node (ref "U3") (pin "P$26") (pinfunction "GND_P$26") (pintype "bidirectional"))
      (node (ref "U3") (pin "P$33") (pinfunction "PGND_P$33") (pintype "bidirectional"))
    )
    (net (code "37") (name "unconnected-(CN1-Pad3)") (class "Default")
      (node (ref "CN1") (pin "3") (pinfunction "3_3") (pintype "bidirectional"))
    )
    (net (code "38") (name "unconnected-(CN2-Pad3)") (class "Default")
      (node (ref "CN2") (pin "3") (pinfunction "3_3") (pintype "bidirectional"))
    )
    (net (code "39") (name "unconnected-(CN4-Pad1)") (class "Default")
      (node (ref "CN4") (pin "1") (pinfunction "1_1") (pintype "passive"))
    )
    (net (code "40") (name "unconnected-(CN4-Pad2)") (class "Default")
      (node (ref "CN4") (pin "2") (pinfunction "2_2") (pintype "passive"))
    )
    (net (code "41") (name "unconnected-(CN4-Pad3)") (class "Default")
      (node (ref "CN4") (pin "3") (pinfunction "3_3") (pintype "passive"))
    )
    (net (code "42") (name "unconnected-(CN5-RX1+-PadP$B11)") (class "Default")
      (node (ref "CN5") (pin "P$B11") (pinfunction "RX1+_P$B11") (pintype "bidirectional"))
    )
    (net (code "43") (name "unconnected-(CN5-RX1--PadP$B10)") (class "Default")
      (node (ref "CN5") (pin "P$B10") (pinfunction "RX1-_P$B10") (pintype "bidirectional"))
    )
    (net (code "44") (name "unconnected-(CN5-RX2+-PadP$A11)") (class "Default")
      (node (ref "CN5") (pin "P$A11") (pinfunction "RX2+_P$A11") (pintype "bidirectional"))
    )
    (net (code "45") (name "unconnected-(CN5-RX2--PadP$A10)") (class "Default")
      (node (ref "CN5") (pin "P$A10") (pinfunction "RX2-_P$A10") (pintype "bidirectional"))
    )
    (net (code "46") (name "unconnected-(CN5-TX1+-PadP$A2)") (class "Default")
      (node (ref "CN5") (pin "P$A2") (pinfunction "TX1+_P$A2") (pintype "bidirectional"))
    )
    (net (code "47") (name "unconnected-(CN5-TX1--PadP$A3)") (class "Default")
      (node (ref "CN5") (pin "P$A3") (pinfunction "TX1-_P$A3") (pintype "bidirectional"))
    )
    (net (code "48") (name "unconnected-(CN5-TX2+-PadP$B2)") (class "Default")
      (node (ref "CN5") (pin "P$B2") (pinfunction "TX2+_P$B2") (pintype "bidirectional"))
    )
    (net (code "49") (name "unconnected-(CN5-TX2--PadP$B3)") (class "Default")
      (node (ref "CN5") (pin "P$B3") (pinfunction "TX2-_P$B3") (pintype "bidirectional"))
    )
    (net (code "50") (name "unconnected-(CN6-Pad1)") (class "Default")
      (node (ref "CN6") (pin "1") (pinfunction "1_1") (pintype "passive"))
    )
    (net (code "51") (name "unconnected-(CN6-Pad2)") (class "Default")
      (node (ref "CN6") (pin "2") (pinfunction "2_2") (pintype "passive"))
    )
    (net (code "52") (name "unconnected-(CN6-Pad7)") (class "Default")
      (node (ref "CN6") (pin "7") (pinfunction "7_7") (pintype "passive"))
    )
    (net (code "53") (name "unconnected-(CN6-Pad8)") (class "Default")
      (node (ref "CN6") (pin "8") (pinfunction "8_8") (pintype "passive"))
    )
    (net (code "54") (name "unconnected-(CN12-1-PadP$1)") (class "Default")
      (node (ref "CN12") (pin "P$1") (pinfunction "1_P$1") (pintype "passive"))
    )
    (net (code "55") (name "unconnected-(CN12-2-PadP$2)") (class "Default")
      (node (ref "CN12") (pin "P$2") (pinfunction "2_P$2") (pintype "passive"))
    )
    (net (code "56") (name "unconnected-(CN12-4-PadP$4)") (class "Default")
      (node (ref "CN12") (pin "P$4") (pinfunction "4_P$4") (pintype "passive"))
    )
    (net (code "57") (name "unconnected-(CN12-8-PadP$8)") (class "Default")
      (node (ref "CN12") (pin "P$8") (pinfunction "8_P$8") (pintype "passive"))
    )
    (net (code "58") (name "unconnected-(CN12-10-PadP$10)") (class "Default")
      (node (ref "CN12") (pin "P$10") (pinfunction "10_P$10") (pintype "passive"))
    )
    (net (code "59") (name "unconnected-(CN12-12-PadP$12)") (class "Default")
      (node (ref "CN12") (pin "P$12") (pinfunction "12_P$12") (pintype "passive"))
    )
    (net (code "60") (name "unconnected-(CN12-13-PadP$13)") (class "Default")
      (node (ref "CN12") (pin "P$13") (pinfunction "13_P$13") (pintype "passive"))
    )
    (net (code "61") (name "unconnected-(CN12-14-PadP$14)") (class "Default")
      (node (ref "CN12") (pin "P$14") (pinfunction "14_P$14") (pintype "passive"))
    )
    (net (code "62") (name "unconnected-(CN13-Pad1)") (class "Default")
      (node (ref "CN13") (pin "1") (pinfunction "1_1") (pintype "passive"))
    )
    (net (code "63") (name "unconnected-(CN13-Pad2)") (class "Default")
      (node (ref "CN13") (pin "2") (pinfunction "2_2") (pintype "passive"))
    )
    (net (code "64") (name "unconnected-(CN13-Pad3)") (class "Default")
      (node (ref "CN13") (pin "3") (pinfunction "3_3") (pintype "passive"))
    )
    (net (code "65") (name "unconnected-(CN13-Pad4)") (class "Default")
      (node (ref "CN13") (pin "4") (pinfunction "4_4") (pintype "passive"))
    )
    (net (code "66") (name "unconnected-(CN13-Pad5)") (class "Default")
      (node (ref "CN13") (pin "5") (pinfunction "5_5") (pintype "passive"))
    )
    (net (code "67") (name "unconnected-(CN13-Pad6)") (class "Default")
      (node (ref "CN13") (pin "6") (pinfunction "6_6") (pintype "passive"))
    )
    (net (code "68") (name "unconnected-(CN13-Pad7)") (class "Default")
      (node (ref "CN13") (pin "7") (pinfunction "7_7") (pintype "passive"))
    )
    (net (code "69") (name "unconnected-(CN13-Pad13)") (class "Default")
      (node (ref "CN13") (pin "13") (pinfunction "13_13") (pintype "passive"))
    )
    (net (code "70") (name "unconnected-(CN13-Pad14)") (class "Default")
      (node (ref "CN13") (pin "14") (pinfunction "14_14") (pintype "passive"))
    )
    (net (code "71") (name "unconnected-(CN14-Pad1)") (class "Default")
      (node (ref "CN14") (pin "1") (pinfunction "1_1") (pintype "passive"))
    )
    (net (code "72") (name "unconnected-(CN14-Pad2)") (class "Default")
      (node (ref "CN14") (pin "2") (pinfunction "2_2") (pintype "passive"))
    )
    (net (code "73") (name "unconnected-(CN14-Pad3)") (class "Default")
      (node (ref "CN14") (pin "3") (pinfunction "3_3") (pintype "passive"))
    )
    (net (code "74") (name "unconnected-(CN14-Pad4)") (class "Default")
      (node (ref "CN14") (pin "4") (pinfunction "4_4") (pintype "passive"))
    )
    (net (code "75") (name "unconnected-(CN14-Pad5)") (class "Default")
      (node (ref "CN14") (pin "5") (pinfunction "5_5") (pintype "passive"))
    )
    (net (code "76") (name "unconnected-(CN14-Pad6)") (class "Default")
      (node (ref "CN14") (pin "6") (pinfunction "6_6") (pintype "passive"))
    )
    (net (code "77") (name "unconnected-(CN14-Pad7)") (class "Default")
      (node (ref "CN14") (pin "7") (pinfunction "7_7") (pintype "passive"))
    )
    (net (code "78") (name "unconnected-(CN14-Pad9)") (class "Default")
      (node (ref "CN14") (pin "9") (pinfunction "9_9") (pintype "passive"))
    )
    (net (code "79") (name "unconnected-(CN14-Pad10)") (class "Default")
      (node (ref "CN14") (pin "10") (pinfunction "10_10") (pintype "passive"))
    )
    (net (code "80") (name "unconnected-(CN14-Pad11)") (class "Default")
      (node (ref "CN14") (pin "11") (pinfunction "11_11") (pintype "passive"))
    )
    (net (code "81") (name "unconnected-(CN14-Pad12)") (class "Default")
      (node (ref "CN14") (pin "12") (pinfunction "12_12") (pintype "passive"))
    )
    (net (code "82") (name "unconnected-(CN14-Pad13)") (class "Default")
      (node (ref "CN14") (pin "13") (pinfunction "13_13") (pintype "passive"))
    )
    (net (code "83") (name "unconnected-(CN14-Pad14)") (class "Default")
      (node (ref "CN14") (pin "14") (pinfunction "14_14") (pintype "passive"))
    )
    (net (code "84") (name "unconnected-(CN18-1-PadP$1)") (class "Default")
      (node (ref "CN18") (pin "P$1") (pinfunction "1_P$1") (pintype "bidirectional"))
    )
    (net (code "85") (name "unconnected-(CN20-DATA+-PadP$3)") (class "Default")
      (node (ref "CN20") (pin "P$3") (pinfunction "DATA+_P$3") (pintype "bidirectional"))
    )
    (net (code "86") (name "unconnected-(CN20-DATA--PadP$2)") (class "Default")
      (node (ref "CN20") (pin "P$2") (pinfunction "DATA-_P$2") (pintype "bidirectional"))
    )
    (net (code "87") (name "unconnected-(CN20-NC-PadP$4)") (class "Default")
      (node (ref "CN20") (pin "P$4") (pinfunction "NC_P$4") (pintype "bidirectional"))
    )
    (net (code "88") (name "unconnected-(CN21-DATA+-PadP$3)") (class "Default")
      (node (ref "CN21") (pin "P$3") (pinfunction "DATA+_P$3") (pintype "bidirectional"))
    )
    (net (code "89") (name "unconnected-(CN21-DATA--PadP$2)") (class "Default")
      (node (ref "CN21") (pin "P$2") (pinfunction "DATA-_P$2") (pintype "bidirectional"))
    )
    (net (code "90") (name "unconnected-(CN21-NC-PadP$4)") (class "Default")
      (node (ref "CN21") (pin "P$4") (pinfunction "NC_P$4") (pintype "bidirectional"))
    )
    (net (code "91") (name "unconnected-(J1-CDN-Pad-2)") (class "Default")
      (node (ref "J1") (pin "-2") (pinfunction "CDN_-2") (pintype "bidirectional"))
    )
    (net (code "92") (name "unconnected-(U3-CH_G-PadP$4)") (class "Default")
      (node (ref "U3") (pin "P$4") (pinfunction "CH_G_P$4") (pintype "bidirectional"))
    )
    (net (code "93") (name "unconnected-(U3-DCH_G-PadP$5)") (class "Default")
      (node (ref "U3") (pin "P$5") (pinfunction "DCH_G_P$5") (pintype "bidirectional"))
    )
    (net (code "94") (name "unconnected-(U3-FB-PadP$14)") (class "Default")
      (node (ref "U3") (pin "P$14") (pinfunction "FB_P$14") (pintype "bidirectional"))
    )
    (net (code "95") (name "unconnected-(U3-GPIO2-PadP$13)") (class "Default")
      (node (ref "U3") (pin "P$13") (pinfunction "GPIO2_P$13") (pintype "bidirectional"))
    )
    (net (code "96") (name "unconnected-(U3-GPIO7-PadP$16)") (class "Default")
      (node (ref "U3") (pin "P$16") (pinfunction "GPIO7_P$16") (pintype "bidirectional"))
    )
    (net (code "97") (name "unconnected-(U3-GPIO8-PadP$15)") (class "Default")
      (node (ref "U3") (pin "P$15") (pinfunction "GPIO8_P$15") (pintype "bidirectional"))
    )
    (net (code "98") (name "unconnected-(U3-INT-PadP$25)") (class "Default")
      (node (ref "U3") (pin "P$25") (pinfunction "INT_P$25") (pintype "bidirectional"))
    )
    (net (code "99") (name "unconnected-(U3-SCL-PadP$21)") (class "Default")
      (node (ref "U3") (pin "P$21") (pinfunction "SCL_P$21") (pintype "bidirectional"))
    )
    (net (code "100") (name "unconnected-(U3-SDA-PadP$20)") (class "Default")
      (node (ref "U3") (pin "P$20") (pinfunction "SDA_P$20") (pintype "bidirectional"))
    )
    (net (code "101") (name "unconnected-(U3-TEST1-PadP$19)") (class "Default")
      (node (ref "U3") (pin "P$19") (pinfunction "TEST1_P$19") (pintype "bidirectional"))
    )
    (net (code "102") (name "unconnected-(U3-TEST2-PadP$22)") (class "Default")
      (node (ref "U3") (pin "P$22") (pinfunction "TEST2_P$22") (pintype "bidirectional"))
    )
    (net (code "103") (name "unconnected-(U3-VCON5V-PadP$6)") (class "Default")
      (node (ref "U3") (pin "P$6") (pinfunction "VCON5V_P$6") (pintype "bidirectional"))
    )
    (net (code "104") (name "unconnected-(X1-Pad2)") (class "Default")
      (node (ref "X1") (pin "2") (pinfunction "2_2") (pintype "passive"))
    )
    (net (code "105") (name "unconnected-(X1-Pad3)") (class "Default")
      (node (ref "X1") (pin "3") (pinfunction "3_3") (pintype "passive"))
    )
    (net (code "106") (name "unconnected-(X2-Pad2)") (class "Default")
      (node (ref "X2") (pin "2") (pinfunction "2_2") (pintype "passive"))
    )
    (net (code "107") (name "unconnected-(X2-Pad3)") (class "Default")
      (node (ref "X2") (pin "3") (pinfunction "3_3") (pintype "passive"))
    )
    (net (code "108") (name "unconnected-(X3-Pad2)") (class "Default")
      (node (ref "X3") (pin "2") (pinfunction "2_2") (pintype "passive"))
    )
    (net (code "109") (name "unconnected-(X3-Pad3)") (class "Default")
      (node (ref "X3") (pin "3") (pinfunction "3_3") (pintype "passive"))
    )
    (net (code "110") (name "unconnected-(X4-Pad2)") (class "Default")
      (node (ref "X4") (pin "2") (pinfunction "2_2") (pintype "passive"))
    )
    (net (code "111") (name "unconnected-(X4-Pad3)") (class "Default")
      (node (ref "X4") (pin "3") (pinfunction "3_3") (pintype "passive"))
    )
  )
)
